# AD835.net
KiCad netlist of a schematic drawn in Altium Designer
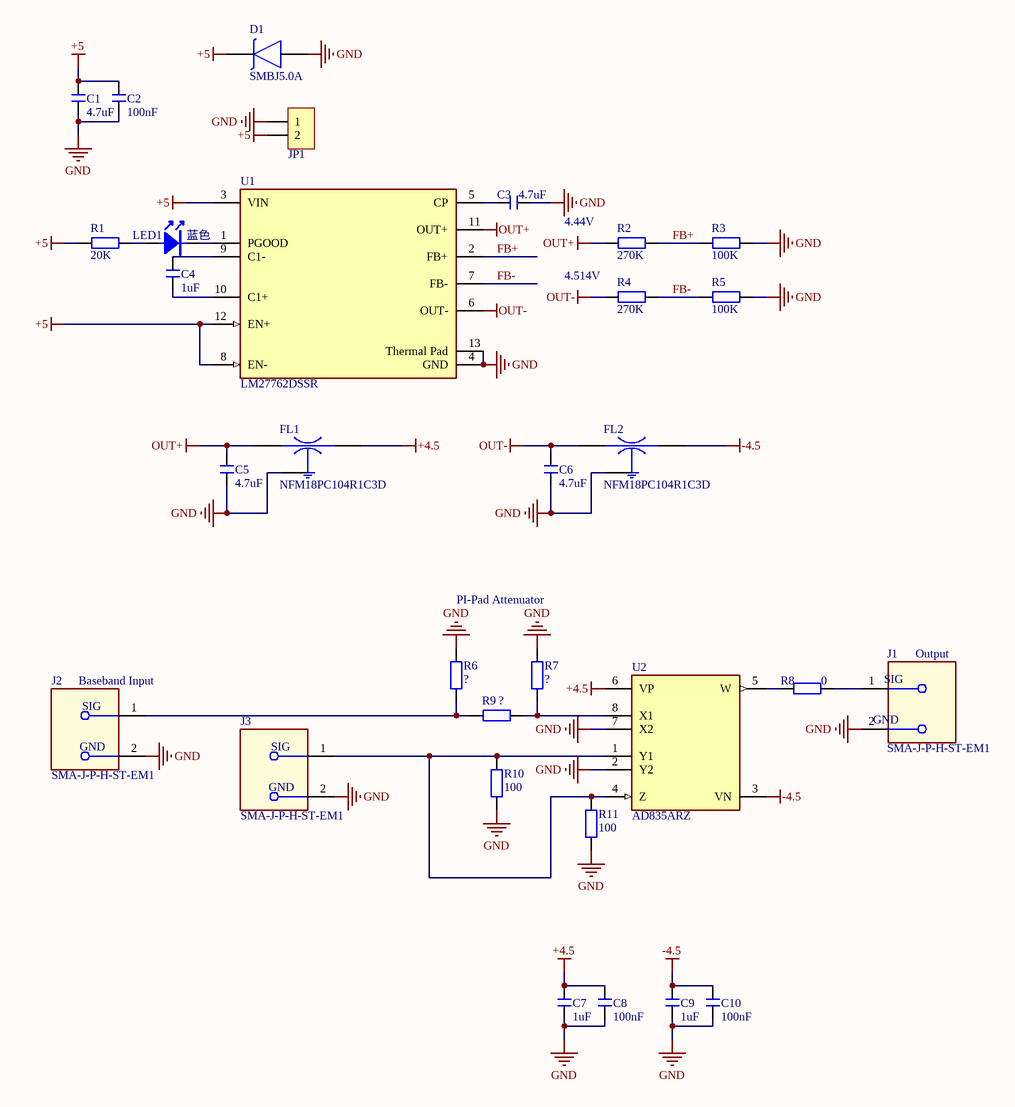
[diagram p0: AD835.SchDoc]

(export (version "E")
  (design (tool "Eeschema 10.0.6"))
  (components
    (comp (ref "C1")
      (value "4.7uF")
      (footprint "C 0603_L")
      (description "贴片电容")
      (libsource (lib "01 - 电容-电阻-电感") (part "C"))
    )
    (comp (ref "C2")
      (value "100nF")
      (footprint "C 0603_L")
      (description "贴片电容")
      (libsource (lib "01 - 电容-电阻-电感") (part "C"))
    )
    (comp (ref "C3")
      (value "4.7uF")
      (footprint "C 0603_L")
      (description "贴片电容")
      (libsource (lib "01 - 电容-电阻-电感") (part "C"))
    )
    (comp (ref "C4")
      (value "1uF")
      (footprint "C 0603_L")
      (description "贴片电容")
      (libsource (lib "01 - 电容-电阻-电感") (part "C"))
    )
    (comp (ref "C5")
      (value "4.7uF")
      (footprint "C 0603_L")
      (description "贴片电容")
      (libsource (lib "01 - 电容-电阻-电感") (part "C"))
    )
    (comp (ref "C6")
      (value "4.7uF")
      (footprint "C 0603_L")
      (description "贴片电容")
      (libsource (lib "01 - 电容-电阻-电感") (part "C"))
    )
    (comp (ref "C7")
      (value "1uF")
      (footprint "C 0603_L")
      (description "贴片电容")
      (libsource (lib "01 - 电容-电阻-电感") (part "C"))
    )
    (comp (ref "C8")
      (value "100nF")
      (footprint "C 0603_L")
      (description "贴片电容")
      (libsource (lib "01 - 电容-电阻-电感") (part "C"))
    )
    (comp (ref "C9")
      (value "1uF")
      (footprint "C 0603_L")
      (description "贴片电容")
      (libsource (lib "01 - 电容-电阻-电感") (part "C"))
    )
    (comp (ref "C10")
      (value "100nF")
      (footprint "C 0603_L")
      (description "贴片电容")
      (libsource (lib "01 - 电容-电阻-电感") (part "C"))
    )
    (comp (ref "D1")
      (value "SMBJ5.0A")
      (footprint "SMBJX.XA_Series_TVS:SMBJ5.0A")
      (description "SMBJX.XA Seires TVS")
      (fields (field (name "MF") "Littelfuse"))
      (libsource (lib "SMBJX.XA_Series_TVS") (part "SMBJ5.0A"))
    )
    (comp (ref "FL1")
      (value "NFM18PC104R1C3D")
      (footprint "FIL_NFM18PC104R1C3D")
      (description "SMD Capacitor with Capacitance: 0.10uF Tol. 20%. Rated Voltage: 16Vdc")
      (fields (field (name "MF") "Murata") (field (name "DIGI-KEY_PART_NUMBER") "490-6969-1-ND"))
      (libsource (lib "NFM18PC104R1C3D") (part "NFM18PC104R1C3D"))
    )
    (comp (ref "FL2")
      (value "NFM18PC104R1C3D")
      (footprint "FIL_NFM18PC104R1C3D")
      (description "SMD Capacitor with Capacitance: 0.10uF Tol. 20%. Rated Voltage: 16Vdc")
      (fields (field (name "MF") "Murata") (field (name "DIGI-KEY_PART_NUMBER") "490-6969-1-ND"))
      (libsource (lib "NFM18PC104R1C3D") (part "NFM18PC104R1C3D"))
    )
    (comp (ref "J1")
      (value "SMA-J-P-H-ST-EM1")
      (footprint "FP-SMA-J-P-H-ST-EM1-MFG")
      (description "CONN SMA JACK STR 50OHM EDGE MNT")
      (libsource (lib "") (part "CMP-02754-000006-1_1"))
    )
    (comp (ref "J2")
      (value "SMA-J-P-H-ST-EM1")
      (footprint "FP-SMA-J-P-H-ST-EM1-MFG")
      (description "CONN SMA JACK STR 50OHM EDGE MNT")
      (libsource (lib "卧式SMA") (part "CMP-02754-000006-1"))
    )
    (comp (ref "J3")
      (value "SMA-J-P-H-ST-EM1")
      (footprint "FP-SMA-J-P-H-ST-EM1-MFG")
      (description "CONN SMA JACK STR 50OHM EDGE MNT")
      (libsource (lib "卧式SMA") (part "CMP-02754-000006-1"))
    )
    (comp (ref "JP1")
      (value "HDR-1X2")
      (footprint "KF2510-LI-2P")
      (description "2P接插件")
      (libsource (lib "18 - 接插件-脚距2.54mm (100mil) ") (part "Header 2"))
    )
    (comp (ref "LED1")
      (value "蓝色")
      (footprint "LED 0603B")
      (description "贴片LED")
      (libsource (lib "02 - 二极管(LED)-三极管-整流桥") (part "LED-SMD"))
    )
    (comp (ref "R1")
      (value "20K")
      (footprint "R 0603_L")
      (description "贴片电阻")
      (libsource (lib "01 - 电容-电阻-电感") (part "R"))
    )
    (comp (ref "R2")
      (value "270K")
      (footprint "R 0603_L")
      (description "贴片电阻")
      (libsource (lib "01 - 电容-电阻-电感") (part "R"))
    )
    (comp (ref "R3")
      (value "100K")
      (footprint "R 0603_L")
      (description "贴片电阻")
      (libsource (lib "01 - 电容-电阻-电感") (part "R"))
    )
    (comp (ref "R4")
      (value "270K")
      (footprint "R 0603_L")
      (description "贴片电阻")
      (libsource (lib "01 - 电容-电阻-电感") (part "R"))
    )
    (comp (ref "R5")
      (value "100K")
      (footprint "R 0603_L")
      (description "贴片电阻")
      (libsource (lib "01 - 电容-电阻-电感") (part "R"))
    )
    (comp (ref "R6")
      (value "?")
      (footprint "R 0603_L")
      (description "贴片电阻")
      (libsource (lib "01 - 电容-电阻-电感") (part "R"))
    )
    (comp (ref "R7")
      (value "?")
      (footprint "R 0603_L")
      (description "贴片电阻")
      (libsource (lib "01 - 电容-电阻-电感") (part "R"))
    )
    (comp (ref "R8")
      (value "0")
      (footprint "R 0603_L")
      (description "贴片电阻")
      (libsource (lib "01 - 电容-电阻-电感") (part "R"))
    )
    (comp (ref "R9")
      (value "?")
      (footprint "R 0603_L")
      (description "贴片电阻")
      (libsource (lib "01 - 电容-电阻-电感") (part "R"))
    )
    (comp (ref "R10")
      (value "100")
      (footprint "R 0603_L")
      (description "贴片电阻")
      (libsource (lib "01 - 电容-电阻-电感") (part "R"))
    )
    (comp (ref "R11")
      (value "100")
      (footprint "R 0603_L")
      (description "贴片电阻")
      (libsource (lib "01 - 电容-电阻-电感") (part "R"))
    )
    (comp (ref "U1")
      (value "LM27762DSSR")
      (footprint "FP-DSS0012B-MFG")
      (description "IC REG CHARGE PUMP ADJ DL 12WSON")
      (libsource (lib "LM27762DSSR") (part "LM27762DSSR"))
    )
    (comp (ref "U2")
      (value "AD835ARZ")
      (footprint "FP-R-8-IPC_C")
      (description "ANALOG MULTIPLIER OR DIVIDER, 25")
      (libsource (lib "AD835ARZ") (part "AD835ARZ"))
    )
  )
  (nets
    (net (code "1") (name "+4.5") (class "Default")
      (node (ref "C7") (pin "2") (pinfunction "2_2") (pintype "passive"))
      (node (ref "C8") (pin "2") (pinfunction "2_2") (pintype "passive"))
      (node (ref "FL1") (pin "3") (pinfunction "OUT_3") (pintype "passive"))
      (node (ref "U2") (pin "6") (pinfunction "VP_6") (pintype "power_in"))
    )
    (net (code "2") (name "+5") (class "Default")
      (node (ref "C1") (pin "2") (pinfunction "2_2") (pintype "passive"))
      (node (ref "C2") (pin "2") (pinfunction "2_2") (pintype "passive"))
      (node (ref "D1") (pin "1") (pinfunction "K_1") (pintype "passive"))
      (node (ref "JP1") (pin "2") (pinfunction "2_2") (pintype "passive"))
      (node (ref "R1") (pin "1") (pinfunction "1_1") (pintype "passive"))
      (node (ref "U1") (pin "12") (pinfunction "EN+_12") (pintype "input"))
      (node (ref "U1") (pin "3") (pinfunction "VIN_3") (pintype "power_in"))
      (node (ref "U1") (pin "8") (pinfunction "EN-_8") (pintype "input"))
    )
    (net (code "3") (name "-4.5") (class "Default")
      (node (ref "C10") (pin "2") (pinfunction "2_2") (pintype "passive"))
      (node (ref "C9") (pin "2") (pinfunction "2_2") (pintype "passive"))
      (node (ref "FL2") (pin "3") (pinfunction "OUT_3") (pintype "passive"))
      (node (ref "U2") (pin "3") (pinfunction "VN_3") (pintype "power_in"))
    )
    (net (code "4") (name "/FB+") (class "Default")
      (node (ref "R2") (pin "2") (pinfunction "2_2") (pintype "passive"))
      (node (ref "R3") (pin "1") (pinfunction "1_1") (pintype "passive"))
      (node (ref "U1") (pin "2") (pinfunction "FB+_2") (pintype "passive"))
    )
    (net (code "5") (name "/FB-") (class "Default")
      (node (ref "R4") (pin "2") (pinfunction "2_2") (pintype "passive"))
      (node (ref "R5") (pin "1") (pinfunction "1_1") (pintype "passive"))
      (node (ref "U1") (pin "7") (pinfunction "FB-_7") (pintype "passive"))
    )
    (net (code "6") (name "GND") (class "Default")
      (node (ref "C1") (pin "1") (pinfunction "1_1") (pintype "passive"))
      (node (ref "C10") (pin "1") (pinfunction "1_1") (pintype "passive"))
      (node (ref "C2") (pin "1") (pinfunction "1_1") (pintype "passive"))
      (node (ref "C3") (pin "1") (pinfunction "1_1") (pintype "passive"))
      (node (ref "C5") (pin "2") (pinfunction "2_2") (pintype "passive"))
      (node (ref "C6") (pin "2") (pinfunction "2_2") (pintype "passive"))
      (node (ref "C7") (pin "1") (pinfunction "1_1") (pintype "passive"))
      (node (ref "C8") (pin "1") (pinfunction "1_1") (pintype "passive"))
      (node (ref "C9") (pin "1") (pinfunction "1_1") (pintype "passive"))
      (node (ref "D1") (pin "2") (pinfunction "A_2") (pintype "passive"))
      (node (ref "FL1") (pin "2") (pinfunction "GND_2") (pintype "power_in"))
      (node (ref "FL2") (pin "2") (pinfunction "GND_2") (pintype "power_in"))
      (node (ref "J1") (pin "2") (pinfunction "MNT_1_2") (pintype "passive"))
      (node (ref "J2") (pin "2") (pinfunction "MNT_1_2") (pintype "passive"))
      (node (ref "J3") (pin "2") (pinfunction "MNT_1_2") (pintype "passive"))
      (node (ref "JP1") (pin "1") (pinfunction "1_1") (pintype "passive"))
      (node (ref "R10") (pin "1") (pinfunction "1_1") (pintype "passive"))
      (node (ref "R11") (pin "1") (pinfunction "1_1") (pintype "passive"))
      (node (ref "R3") (pin "2") (pinfunction "2_2") (pintype "passive"))
      (node (ref "R5") (pin "2") (pinfunction "2_2") (pintype "passive"))
      (node (ref "R6") (pin "2") (pinfunction "2_2") (pintype "passive"))
      (node (ref "R7") (pin "2") (pinfunction "2_2") (pintype "passive"))
      (node (ref "U1") (pin "13") (pinfunction "Thermal_Pad_13") (pintype "passive"))
      (node (ref "U1") (pin "4") (pinfunction "GND_4") (pintype "power_in"))
      (node (ref "U2") (pin "2") (pinfunction "Y2_2") (pintype "tri_state"))
      (node (ref "U2") (pin "7") (pinfunction "X2_7") (pintype "tri_state"))
    )
    (net (code "7") (name "Net-(J1-Pad1)") (class "Default")
      (node (ref "J1") (pin "1") (pinfunction "1_1") (pintype "passive"))
      (node (ref "R8") (pin "2") (pinfunction "2_2") (pintype "passive"))
    )
    (net (code "8") (name "Net-(J2-Pad1)") (class "Default")
      (node (ref "J2") (pin "1") (pinfunction "1_1") (pintype "passive"))
      (node (ref "R6") (pin "1") (pinfunction "1_1") (pintype "passive"))
      (node (ref "R9") (pin "1") (pinfunction "1_1") (pintype "passive"))
    )
    (net (code "9") (name "Net-(LED1-A)") (class "Default")
      (node (ref "LED1") (pin "1") (pinfunction "A_1") (pintype "passive"))
      (node (ref "R1") (pin "2") (pinfunction "2_2") (pintype "passive"))
    )
    (net (code "10") (name "Net-(LED1-K)") (class "Default")
      (node (ref "LED1") (pin "2") (pinfunction "K_2") (pintype "passive"))
      (node (ref "U1") (pin "1") (pinfunction "PGOOD_1") (pintype "open_collector"))
    )
    (net (code "11") (name "Net-(U1-C1+)") (class "Default")
      (node (ref "C4") (pin "1") (pinfunction "1_1") (pintype "passive"))
      (node (ref "U1") (pin "10") (pinfunction "C1+_10") (pintype "passive"))
    )
    (net (code "12") (name "Net-(U1-C1-)") (class "Default")
      (node (ref "C4") (pin "2") (pinfunction "2_2") (pintype "passive"))
      (node (ref "U1") (pin "9") (pinfunction "C1-_9") (pintype "passive"))
    )
    (net (code "13") (name "Net-(U1-CP)") (class "Default")
      (node (ref "C3") (pin "2") (pinfunction "2_2") (pintype "passive"))
      (node (ref "U1") (pin "5") (pinfunction "CP_5") (pintype "passive"))
    )
    (net (code "14") (name "Net-(U2-W)") (class "Default")
      (node (ref "R8") (pin "1") (pinfunction "1_1") (pintype "passive"))
      (node (ref "U2") (pin "5") (pinfunction "W_5") (pintype "output"))
    )
    (net (code "15") (name "Net-(U2-X1)") (class "Default")
      (node (ref "R7") (pin "1") (pinfunction "1_1") (pintype "passive"))
      (node (ref "R9") (pin "2") (pinfunction "2_2") (pintype "passive"))
      (node (ref "U2") (pin "8") (pinfunction "X1_8") (pintype "tri_state"))
    )
    (net (code "16") (name "Net-(U2-Y1)") (class "Default")
      (node (ref "J3") (pin "1") (pinfunction "1_1") (pintype "passive"))
      (node (ref "R10") (pin "2") (pinfunction "2_2") (pintype "passive"))
      (node (ref "R11") (pin "2") (pinfunction "2_2") (pintype "passive"))
      (node (ref "U2") (pin "1") (pinfunction "Y1_1") (pintype "tri_state"))
      (node (ref "U2") (pin "4") (pinfunction "Z_4") (pintype "input"))
    )
    (net (code "17") (name "OUT+") (class "Default")
      (node (ref "C5") (pin "1") (pinfunction "1_1") (pintype "passive"))
      (node (ref "FL1") (pin "1") (pinfunction "IN_1") (pintype "passive"))
      (node (ref "R2") (pin "1") (pinfunction "1_1") (pintype "passive"))
      (node (ref "U1") (pin "11") (pinfunction "OUT+_11") (pintype "passive"))
    )
    (net (code "18") (name "OUT-") (class "Default")
      (node (ref "C6") (pin "1") (pinfunction "1_1") (pintype "passive"))
      (node (ref "FL2") (pin "1") (pinfunction "IN_1") (pintype "passive"))
      (node (ref "R4") (pin "1") (pinfunction "1_1") (pintype "passive"))
      (node (ref "U1") (pin "6") (pinfunction "OUT-_6") (pintype "passive"))
    )
  )
)
